# programmer.net
KiCad netlist of a schematic drawn in EAGLE
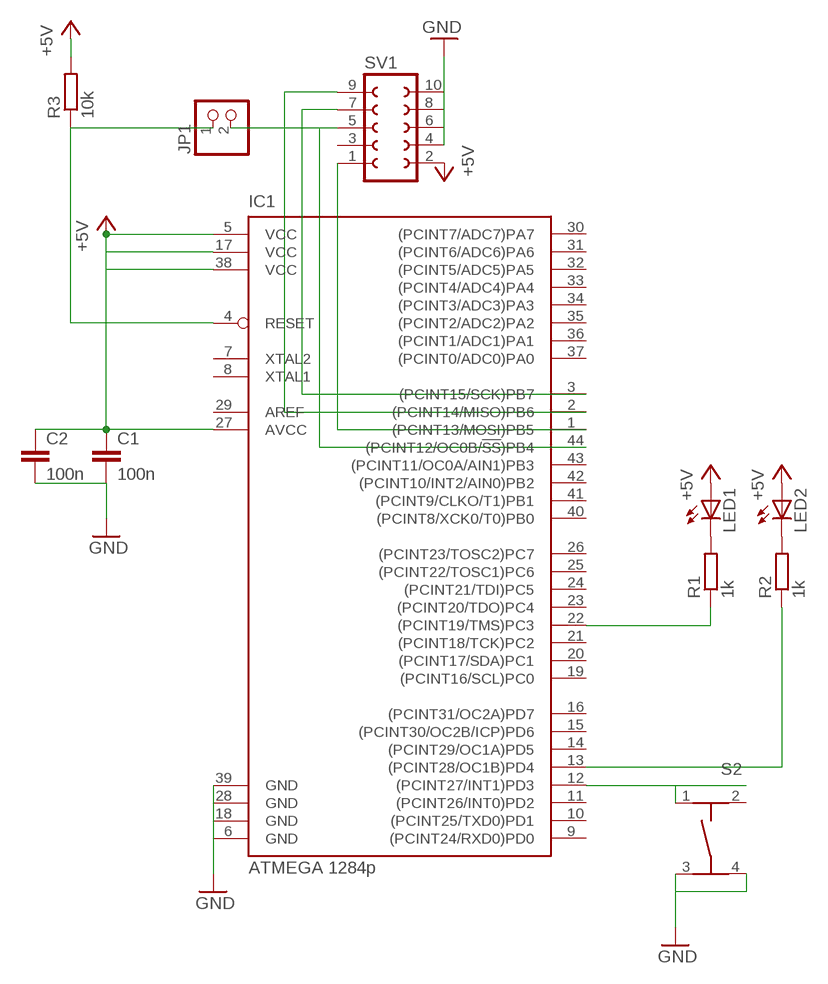
[diagram p0: schematic, sheet 1]

(export (version "E")
  (design (tool "Eeschema 10.0.6"))
  (components
    (comp (ref "C1")
      (value "100n")
      (footprint "eagle-import:C0603")
      (libsource (lib "eagle-import") (part "C-EUC0603"))
    )
    (comp (ref "C2")
      (value "100n")
      (footprint "eagle-import:C0603")
      (libsource (lib "eagle-import") (part "C-EUC0603"))
    )
    (comp (ref "IC1")
      (value "ATMEGA 1284p")
      (footprint "eagle-import:TQFP44")
      (fields (field (name "MPN") "ATMEGA644PV-10AU"))
      (libsource (lib "eagle-import") (part "ATMEGA644A"))
    )
    (comp (ref "JP1")
      (value "PINHD-1X2")
      (footprint "eagle-import:1X02")
      (libsource (lib "eagle-import") (part "PINHD-1X2"))
    )
    (comp (ref "LED1")
      (value "LED")
      (footprint "eagle-import:SMARTLED-TTW")
      (libsource (lib "eagle-import") (part "LED"))
    )
    (comp (ref "LED2")
      (value "LED")
      (footprint "eagle-import:SMARTLED-TTW")
      (libsource (lib "eagle-import") (part "LED"))
    )
    (comp (ref "R1")
      (value "1k")
      (footprint "eagle-import:R0603")
      (libsource (lib "eagle-import") (part "R-EU_R0603"))
    )
    (comp (ref "R2")
      (value "1k")
      (footprint "eagle-import:R0603")
      (libsource (lib "eagle-import") (part "R-EU_R0603"))
    )
    (comp (ref "R3")
      (value "10k")
      (footprint "eagle-import:R0603")
      (libsource (lib "eagle-import") (part "R-EU_R0603"))
    )
    (comp (ref "S2")
      (value "TASTER-9314_SMD")
      (footprint "eagle-import:TASTER-9314_SMD")
      (libsource (lib "eagle-import") (part "TASTER-9314_SMD"))
    )
    (comp (ref "SV1")
      (value "FE05-2W")
      (footprint "eagle-import:FE05-2W")
      (libsource (lib "eagle-import") (part "FE05-2W"))
    )
  )
  (nets
    (net (code "1") (name "+5V") (class "Default")
      (node (ref "C1") (pin "1") (pinfunction "1_1") (pintype "passive"))
      (node (ref "C2") (pin "1") (pinfunction "1_1") (pintype "passive"))
      (node (ref "IC1") (pin "17") (pinfunction "VCC_17") (pintype "power_in"))
      (node (ref "IC1") (pin "27") (pinfunction "AVCC_27") (pintype "power_in"))
      (node (ref "IC1") (pin "38") (pinfunction "VCC_38") (pintype "power_in"))
      (node (ref "IC1") (pin "5") (pinfunction "VCC_5") (pintype "power_in"))
      (node (ref "LED1") (pin "A@1") (pinfunction "A_A@1") (pintype "passive"))
      (node (ref "LED2") (pin "A@1") (pinfunction "A_A@1") (pintype "passive"))
      (node (ref "R3") (pin "2") (pinfunction "2_2") (pintype "passive"))
      (node (ref "SV1") (pin "2") (pinfunction "2_2") (pintype "passive"))
    )
    (net (code "2") (name "GND") (class "Default")
      (node (ref "C1") (pin "2") (pinfunction "2_2") (pintype "passive"))
      (node (ref "C2") (pin "2") (pinfunction "2_2") (pintype "passive"))
      (node (ref "IC1") (pin "18") (pinfunction "GND_18") (pintype "power_in"))
      (node (ref "IC1") (pin "28") (pinfunction "GND_28") (pintype "power_in"))
      (node (ref "IC1") (pin "39") (pinfunction "GND_39") (pintype "power_in"))
      (node (ref "IC1") (pin "6") (pinfunction "GND_6") (pintype "power_in"))
      (node (ref "S2") (pin "3") (pinfunction "3_3") (pintype "passive"))
      (node (ref "S2") (pin "4") (pinfunction "4_4") (pintype "passive"))
      (node (ref "SV1") (pin "10") (pinfunction "10_10") (pintype "passive"))
      (node (ref "SV1") (pin "4") (pinfunction "4_4") (pintype "passive"))
      (node (ref "SV1") (pin "6") (pinfunction "6_6") (pintype "passive"))
      (node (ref "SV1") (pin "8") (pinfunction "8_8") (pintype "passive"))
    )
    (net (code "3") (name "Net-(IC1-(PCINT12{slash}OC0B{slash}~{SS})PB4)") (class "Default")
      (node (ref "IC1") (pin "44") (pinfunction "(PCINT12/OC0B/~{SS})PB4_44") (pintype "bidirectional"))
      (node (ref "JP1") (pin "2") (pinfunction "2_2") (pintype "passive"))
      (node (ref "SV1") (pin "5") (pinfunction "5_5") (pintype "passive"))
    )
    (net (code "4") (name "Net-(IC1-(PCINT13{slash}MOSI)PB5)") (class "Default")
      (node (ref "IC1") (pin "1") (pinfunction "(PCINT13/MOSI)PB5_1") (pintype "bidirectional"))
      (node (ref "SV1") (pin "1") (pinfunction "1_1") (pintype "passive"))
    )
    (net (code "5") (name "Net-(IC1-(PCINT14{slash}MISO)PB6)") (class "Default")
      (node (ref "IC1") (pin "2") (pinfunction "(PCINT14/MISO)PB6_2") (pintype "bidirectional"))
      (node (ref "SV1") (pin "9") (pinfunction "9_9") (pintype "passive"))
    )
    (net (code "6") (name "Net-(IC1-(PCINT15{slash}SCK)PB7)") (class "Default")
      (node (ref "IC1") (pin "3") (pinfunction "(PCINT15/SCK)PB7_3") (pintype "bidirectional"))
      (node (ref "SV1") (pin "7") (pinfunction "7_7") (pintype "passive"))
    )
    (net (code "7") (name "Net-(IC1-(PCINT19{slash}TMS)PC3)") (class "Default")
      (node (ref "IC1") (pin "22") (pinfunction "(PCINT19/TMS)PC3_22") (pintype "output"))
      (node (ref "R1") (pin "1") (pinfunction "1_1") (pintype "passive"))
    )
    (net (code "8") (name "Net-(IC1-(PCINT27{slash}INT1)PD3)") (class "Default")
      (node (ref "IC1") (pin "12") (pinfunction "(PCINT27/INT1)PD3_12") (pintype "bidirectional"))
      (node (ref "S2") (pin "1") (pinfunction "1_1") (pintype "passive"))
    )
    (net (code "9") (name "Net-(IC1-(PCINT28{slash}OC1B)PD4)") (class "Default")
      (node (ref "IC1") (pin "13") (pinfunction "(PCINT28/OC1B)PD4_13") (pintype "bidirectional"))
      (node (ref "R2") (pin "1") (pinfunction "1_1") (pintype "passive"))
    )
    (net (code "10") (name "Net-(IC1-RESET)") (class "Default")
      (node (ref "IC1") (pin "4") (pinfunction "RESET_4") (pintype "input"))
      (node (ref "JP1") (pin "1") (pinfunction "1_1") (pintype "passive"))
      (node (ref "R3") (pin "1") (pinfunction "1_1") (pintype "passive"))
    )
    (net (code "11") (name "Net-(LED1-C)") (class "Default")
      (node (ref "LED1") (pin "C@1") (pinfunction "C_C@1") (pintype "passive"))
      (node (ref "R1") (pin "2") (pinfunction "2_2") (pintype "passive"))
    )
    (net (code "12") (name "Net-(LED2-C)") (class "Default")
      (node (ref "LED2") (pin "C@1") (pinfunction "C_C@1") (pintype "passive"))
      (node (ref "R2") (pin "2") (pinfunction "2_2") (pintype "passive"))
    )
    (net (code "13") (name "unconnected-(IC1-(PCINT0{slash}ADC0)PA0-Pad37)") (class "Default")
      (node (ref "IC1") (pin "37") (pinfunction "(PCINT0/ADC0)PA0_37") (pintype "bidirectional"))
    )
    (net (code "14") (name "unconnected-(IC1-(PCINT1{slash}ADC1)PA1-Pad36)") (class "Default")
      (node (ref "IC1") (pin "36") (pinfunction "(PCINT1/ADC1)PA1_36") (pintype "bidirectional"))
    )
    (net (code "15") (name "unconnected-(IC1-(PCINT2{slash}ADC2)PA2-Pad35)") (class "Default")
      (node (ref "IC1") (pin "35") (pinfunction "(PCINT2/ADC2)PA2_35") (pintype "bidirectional"))
    )
    (net (code "16") (name "unconnected-(IC1-(PCINT3{slash}ADC3)PA3-Pad34)") (class "Default")
      (node (ref "IC1") (pin "34") (pinfunction "(PCINT3/ADC3)PA3_34") (pintype "bidirectional"))
    )
    (net (code "17") (name "unconnected-(IC1-(PCINT4{slash}ADC4)PA4-Pad33)") (class "Default")
      (node (ref "IC1") (pin "33") (pinfunction "(PCINT4/ADC4)PA4_33") (pintype "bidirectional"))
    )
    (net (code "18") (name "unconnected-(IC1-(PCINT5{slash}ADC5)PA5-Pad32)") (class "Default")
      (node (ref "IC1") (pin "32") (pinfunction "(PCINT5/ADC5)PA5_32") (pintype "bidirectional"))
    )
    (net (code "19") (name "unconnected-(IC1-(PCINT6{slash}ADC6)PA6-Pad31)") (class "Default")
      (node (ref "IC1") (pin "31") (pinfunction "(PCINT6/ADC6)PA6_31") (pintype "bidirectional"))
    )
    (net (code "20") (name "unconnected-(IC1-(PCINT7{slash}ADC7)PA7-Pad30)") (class "Default")
      (node (ref "IC1") (pin "30") (pinfunction "(PCINT7/ADC7)PA7_30") (pintype "bidirectional"))
    )
    (net (code "21") (name "unconnected-(IC1-(PCINT8{slash}XCK0{slash}T0)PB0-Pad40)") (class "Default")
      (node (ref "IC1") (pin "40") (pinfunction "(PCINT8/XCK0/T0)PB0_40") (pintype "bidirectional"))
    )
    (net (code "22") (name "unconnected-(IC1-(PCINT9{slash}CLKO{slash}T1)PB1-Pad41)") (class "Default")
      (node (ref "IC1") (pin "41") (pinfunction "(PCINT9/CLKO/T1)PB1_41") (pintype "bidirectional"))
    )
    (net (code "23") (name "unconnected-(IC1-(PCINT10{slash}INT2{slash}AIN0)PB2-Pad42)") (class "Default")
      (node (ref "IC1") (pin "42") (pinfunction "(PCINT10/INT2/AIN0)PB2_42") (pintype "bidirectional"))
    )
    (net (code "24") (name "unconnected-(IC1-(PCINT11{slash}OC0A{slash}AIN1)PB3-Pad43)") (class "Default")
      (node (ref "IC1") (pin "43") (pinfunction "(PCINT11/OC0A/AIN1)PB3_43") (pintype "bidirectional"))
    )
    (net (code "25") (name "unconnected-(IC1-(PCINT16{slash}SCL)PC0-Pad19)") (class "Default")
      (node (ref "IC1") (pin "19") (pinfunction "(PCINT16/SCL)PC0_19") (pintype "output"))
    )
    (net (code "26") (name "unconnected-(IC1-(PCINT17{slash}SDA)PC1-Pad20)") (class "Default")
      (node (ref "IC1") (pin "20") (pinfunction "(PCINT17/SDA)PC1_20") (pintype "output"))
    )
    (net (code "27") (name "unconnected-(IC1-(PCINT18{slash}TCK)PC2-Pad21)") (class "Default")
      (node (ref "IC1") (pin "21") (pinfunction "(PCINT18/TCK)PC2_21") (pintype "output"))
    )
    (net (code "28") (name "unconnected-(IC1-(PCINT20{slash}TDO)PC4-Pad23)") (class "Default")
      (node (ref "IC1") (pin "23") (pinfunction "(PCINT20/TDO)PC4_23") (pintype "output"))
    )
    (net (code "29") (name "unconnected-(IC1-(PCINT21{slash}TDI)PC5-Pad24)") (class "Default")
      (node (ref "IC1") (pin "24") (pinfunction "(PCINT21/TDI)PC5_24") (pintype "output"))
    )
    (net (code "30") (name "unconnected-(IC1-(PCINT22{slash}TOSC1)PC6-Pad25)") (class "Default")
      (node (ref "IC1") (pin "25") (pinfunction "(PCINT22/TOSC1)PC6_25") (pintype "output"))
    )
    (net (code "31") (name "unconnected-(IC1-(PCINT23{slash}TOSC2)PC7-Pad26)") (class "Default")
      (node (ref "IC1") (pin "26") (pinfunction "(PCINT23/TOSC2)PC7_26") (pintype "output"))
    )
    (net (code "32") (name "unconnected-(IC1-(PCINT24{slash}RXD0)PD0-Pad9)") (class "Default")
      (node (ref "IC1") (pin "9") (pinfunction "(PCINT24/RXD0)PD0_9") (pintype "bidirectional"))
    )
    (net (code "33") (name "unconnected-(IC1-(PCINT25{slash}TXD0)PD1-Pad10)") (class "Default")
      (node (ref "IC1") (pin "10") (pinfunction "(PCINT25/TXD0)PD1_10") (pintype "bidirectional"))
    )
    (net (code "34") (name "unconnected-(IC1-(PCINT26{slash}INT0)PD2-Pad11)") (class "Default")
      (node (ref "IC1") (pin "11") (pinfunction "(PCINT26/INT0)PD2_11") (pintype "bidirectional"))
    )
    (net (code "35") (name "unconnected-(IC1-(PCINT29{slash}OC1A)PD5-Pad14)") (class "Default")
      (node (ref "IC1") (pin "14") (pinfunction "(PCINT29/OC1A)PD5_14") (pintype "bidirectional"))
    )
    (net (code "36") (name "unconnected-(IC1-(PCINT30{slash}OC2B{slash}ICP)PD6-Pad15)") (class "Default")
      (node (ref "IC1") (pin "15") (pinfunction "(PCINT30/OC2B/ICP)PD6_15") (pintype "bidirectional"))
    )
    (net (code "37") (name "unconnected-(IC1-(PCINT31{slash}OC2A)PD7-Pad16)") (class "Default")
      (node (ref "IC1") (pin "16") (pinfunction "(PCINT31/OC2A)PD7_16") (pintype "bidirectional"))
    )
    (net (code "38") (name "unconnected-(IC1-AREF-Pad29)") (class "Default")
      (node (ref "IC1") (pin "29") (pinfunction "AREF_29") (pintype "passive"))
    )
    (net (code "39") (name "unconnected-(IC1-XTAL1-Pad8)") (class "Default")
      (node (ref "IC1") (pin "8") (pinfunction "XTAL1_8") (pintype "bidirectional"))
    )
    (net (code "40") (name "unconnected-(IC1-XTAL2-Pad7)") (class "Default")
      (node (ref "IC1") (pin "7") (pinfunction "XTAL2_7") (pintype "bidirectional"))
    )
    (net (code "41") (name "unconnected-(S2-Pad2)") (class "Default")
      (node (ref "S2") (pin "2") (pinfunction "2_2") (pintype "passive"))
    )
    (net (code "42") (name "unconnected-(SV1-Pad3)") (class "Default")
      (node (ref "SV1") (pin "3") (pinfunction "3_3") (pintype "passive"))
    )
  )
)
